# Main.net
KiCad netlist of a schematic drawn in Altium Designer
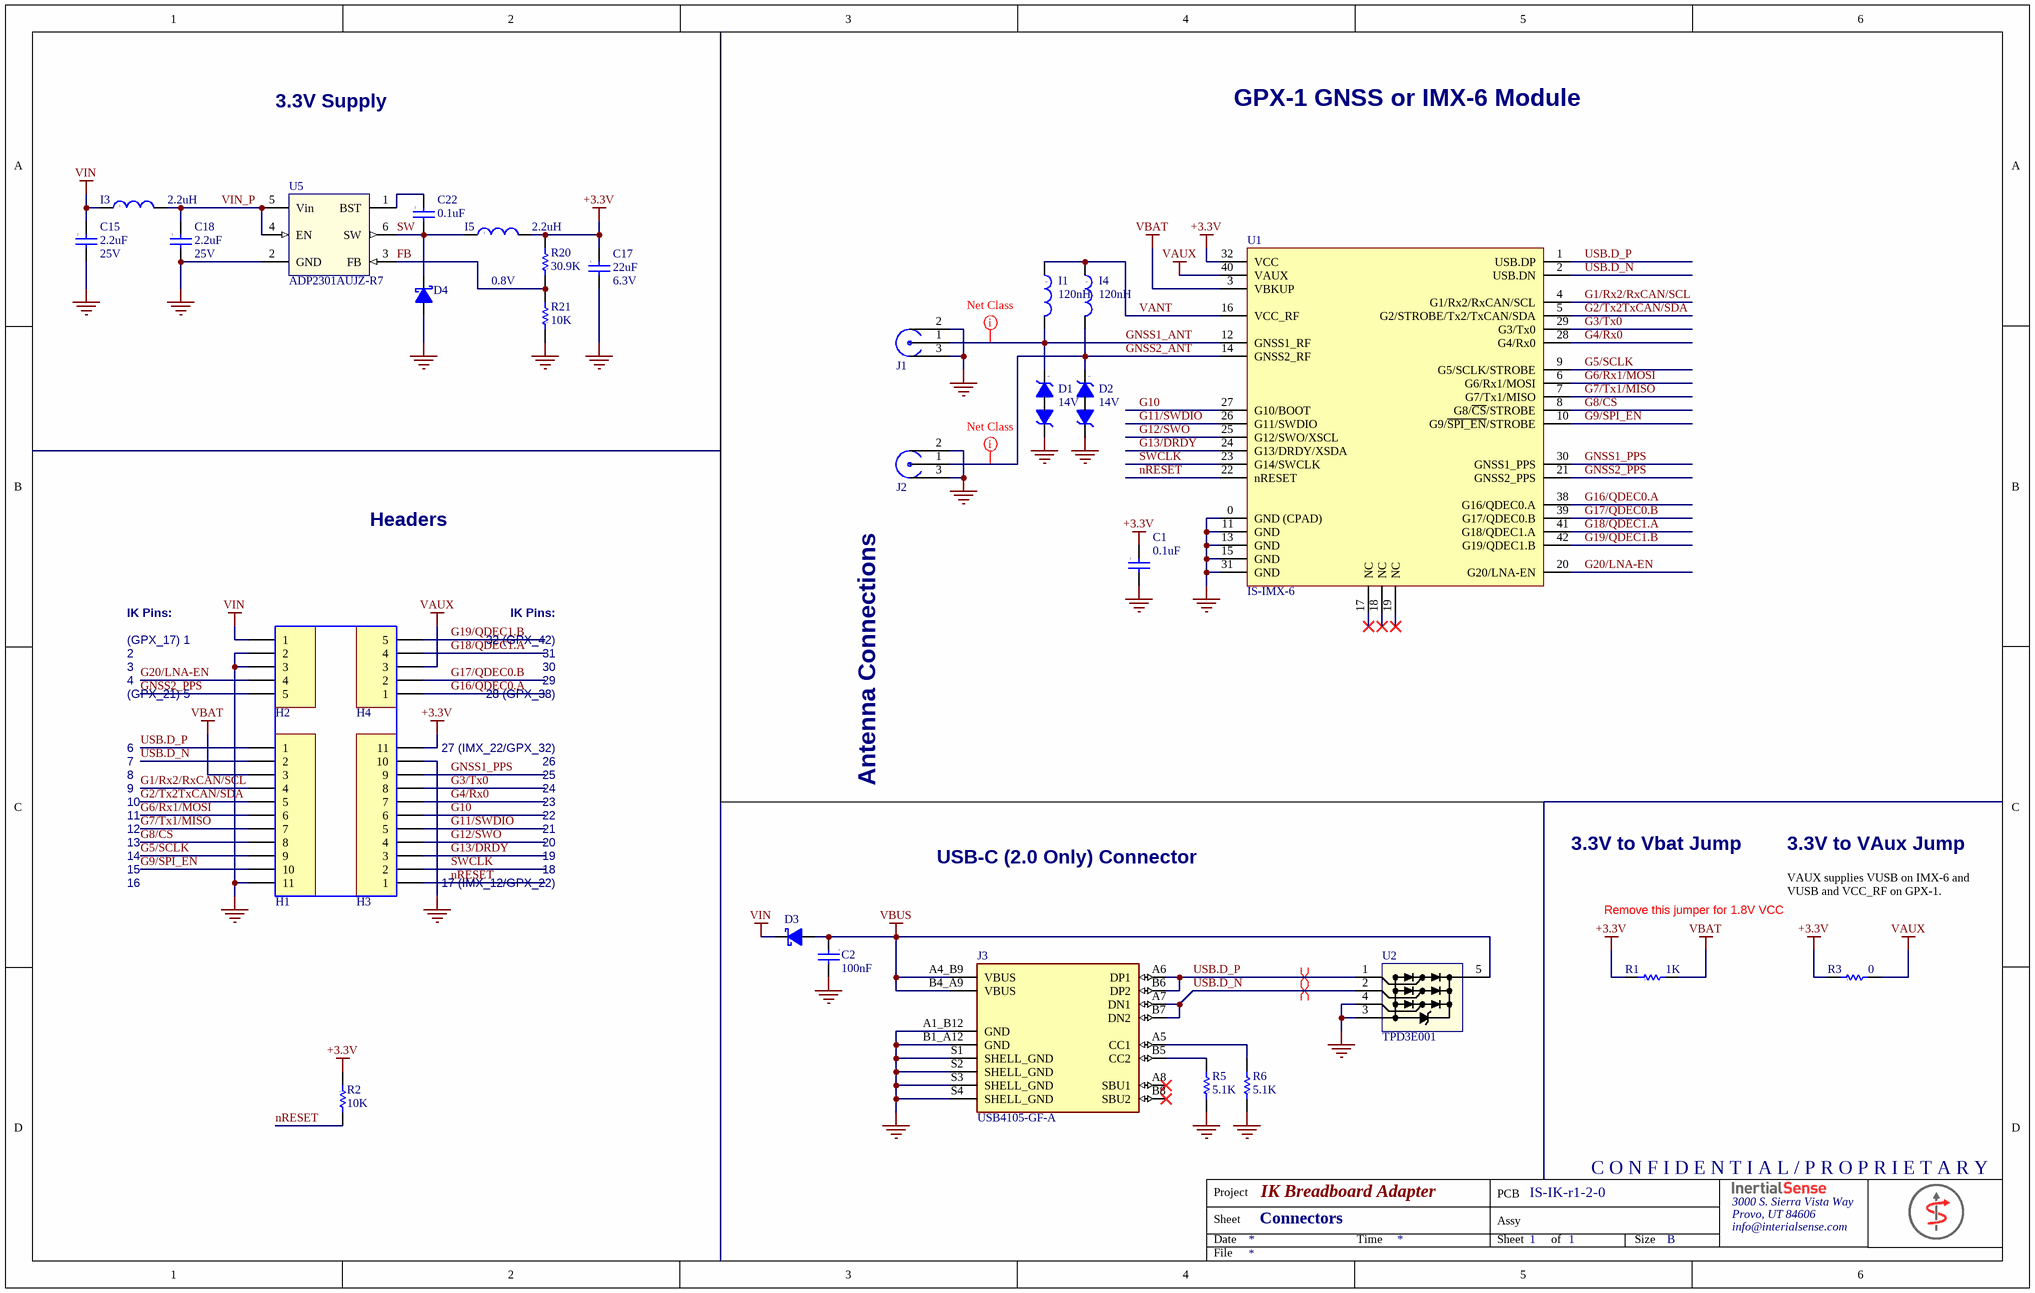
[diagram p0: Main.SchDoc]

(export (version "E")
  (design (tool "Eeschema 10.0.6"))
  (components
    (comp (ref "C1")
      (value "0.1uF")
      (footprint "0402")
      (description "CAP CER .10UF 50V X7R 10% 0402")
      (fields
        (field (name "MANUFACTURER") "TDK Corporation")
        (field (name "MANUFACTURER PART NUMBER") "C1005X7R1H104K")
        (field (name "PUBLISHER") "Altium Limited")
      )
      (libsource (lib "General") (part "Cap"))
    )
    (comp (ref "C2")
      (value "100nF")
      (footprint "0402")
      (description "CAP CER .10UF 50V X7R 10% 0402")
      (fields
        (field (name "MANUFACTURER") "TDK Corporation")
        (field (name "MANUFACTURER PART NUMBER") "C1005X7R1H104K")
        (field (name "PUBLISHER") "Altium Limited")
      )
      (libsource (lib "General") (part "Cap"))
    )
    (comp (ref "C15")
      (value "2.2uF")
      (footprint "0603")
      (description "CAP CER 2.2UF 25V X6S 0603")
      (fields
        (field (name "MANUFACTURER") "Murata")
        (field (name "MANUFACTURER PART NUMBER") "GRT188C81E225KE13D")
        (field (name "VOLTAGE RATING") "25V")
        (field (name "PUBLISHER") "Altium Limited")
      )
      (libsource (lib "General") (part "Cap"))
    )
    (comp (ref "C17")
      (value "22uF")
      (footprint "0603")
      (description "CAP CER 22UF 6.3V X6S 0603")
      (fields
        (field (name "MANUFACTURER") "Murata")
        (field (name "MANUFACTURER PART NUMBER") "GRM188C80J226ME15D")
        (field (name "VOLTAGE RATING") "6.3V")
        (field (name "PUBLISHER") "Altium Limited")
      )
      (libsource (lib "General") (part "Cap"))
    )
    (comp (ref "C18")
      (value "2.2uF")
      (footprint "0603")
      (description "CAP CER 2.2UF 25V X6S 0603")
      (fields
        (field (name "MANUFACTURER") "Murata")
        (field (name "MANUFACTURER PART NUMBER") "GRT188C81E225KE13D")
        (field (name "VOLTAGE RATING") "25V")
        (field (name "PUBLISHER") "Altium Limited")
      )
      (libsource (lib "General") (part "Cap"))
    )
    (comp (ref "C22")
      (value "0.1uF")
      (footprint "0402")
      (description "CAP CER 0.1UF 50V X7R 0402")
      (fields
        (field (name "MANUFACTURER") "TDK")
        (field (name "MANUFACTURER PART NUMBER") "CGA2B3X7R1H104K050BB")
        (field (name "PUBLISHER") "Altium Limited")
      )
      (libsource (lib "General") (part "Cap"))
    )
    (comp (ref "D1")
      (value "Diode - Bidirectional Zener")
      (footprint "R0402")
      (description "LITTELFUSE - PESD0402-140 - DIODE, ESD PROTECTION, 0402, FULL REEL")
      (fields
        (field (name "MANUFACTURER") "Littelfuse")
        (field (name "MANUFACTURER PART NUMBER") "PESD0402-140")
        (field (name "WORKING VOLTAGE") "14V")
      )
      (libsource (lib "General") (part "Diode - Bidirectional Zener"))
    )
    (comp (ref "D2")
      (value "Diode - Bidirectional Zener")
      (footprint "R0402")
      (description "LITTELFUSE - PESD0402-140 - DIODE, ESD PROTECTION, 0402, FULL REEL")
      (fields
        (field (name "MANUFACTURER") "Littelfuse")
        (field (name "MANUFACTURER PART NUMBER") "PESD0402-140")
        (field (name "WORKING VOLTAGE") "14V")
      )
      (libsource (lib "General") (part "Diode - Bidirectional Zener"))
    )
    (comp (ref "D3")
      (value "Diode - Schottky")
      (footprint "D0603B")
      (description "DIODE SCHOTTKY 30V 2A 0603")
      (fields
        (field (name "MANUFACTURER") "Vishay")
        (field (name "MANUFACTURER PART NUMBER") "VSKY20301608-G4-08")
      )
      (libsource (lib "General") (part "Diode - Schottky"))
    )
    (comp (ref "D4")
      (value "Diode - Schottky")
      (footprint "D0603B")
      (description "DIODE SCHOTTKY 30V 2A 0603")
      (fields
        (field (name "MANUFACTURER") "Vishay")
        (field (name "MANUFACTURER PART NUMBER") "VSKY20301608-G4-08")
      )
      (libsource (lib "General") (part "Diode - Schottky"))
    )
    (comp (ref "H1")
      (value "Hdr - 11pin")
      (footprint "Header-.1IN-1x11")
      (description "11 pin header")
      (libsource (lib "") (part "Hdr - 11pin_1"))
    )
    (comp (ref "H2")
      (value "Hdr - 5pin")
      (footprint "Header-.1IN-1x5")
      (description "5 pin header")
      (libsource (lib "") (part "Hdr - 5pin_1"))
    )
    (comp (ref "H3")
      (value "Hdr - 11pin")
      (footprint "Header-.1IN-1x11")
      (description "11 pin header")
      (libsource (lib "IS-IG-BB") (part "Hdr - 11pin"))
    )
    (comp (ref "H4")
      (value "Hdr - 5pin")
      (footprint "Header-.1IN-1x5")
      (description "5 pin header")
      (libsource (lib "IS-IG-BB") (part "Hdr - 5pin"))
    )
    (comp (ref "I1")
      (value "120nH")
      (footprint "0402")
      (description "Inductor RF Chip Wirewound 120nH 5% 100MHz 20Q-Factor 110mA 2.66Ohm DCR 0402 Paper T/R")
      (fields
        (field (name "MANUFACTURER") "Murata")
        (field (name "MANUFACTURER PART NUMBER") "LQW15ANR12J00D")
      )
      (libsource (lib "General") (part "Inductor"))
    )
    (comp (ref "I3")
      (value "2.2uH")
      (footprint "0806")
      (description "FIXED IND 2.2UH 1.2A 110 MOHM")
      (fields
        (field (name "MANUFACTURER") "TDK")
        (field (name "MANUFACTURER PART NUMBER") "MLP2016H2R2MT0S1")
      )
      (libsource (lib "General") (part "Inductor"))
    )
    (comp (ref "I4")
      (value "120nH")
      (footprint "0402")
      (description "Inductor RF Chip Wirewound 120nH 5% 100MHz 20Q-Factor 110mA 2.66Ohm DCR 0402 Paper T/R")
      (fields
        (field (name "MANUFACTURER") "Murata")
        (field (name "MANUFACTURER PART NUMBER") "LQW15ANR12J00D")
      )
      (libsource (lib "General") (part "Inductor"))
    )
    (comp (ref "I5")
      (value "2.2uH")
      (footprint "0806")
      (description "FIXED IND 2.2UH 1.2A 110 MOHM")
      (fields
        (field (name "MANUFACTURER") "TDK")
        (field (name "MANUFACTURER PART NUMBER") "MLP2016H2R2MT0S1")
      )
      (libsource (lib "General") (part "Inductor"))
    )
    (comp (ref "J1")
      (value "RF - GND x 2")
      (footprint "RF UMC SMD")
      (description "CONN UMC RCPT STR 50 OHM SMD")
      (fields
        (field (name "MANUFACTURER") "Emerson Network Power Connectivity Johnson")
        (field (name "MANUFACTURER PART NUMBER") "128-0711-201")
      )
      (libsource (lib "Connectors") (part "RF - GND x 2"))
    )
    (comp (ref "J2")
      (value "RF - GND x 2")
      (footprint "RF UMC SMD")
      (description "CONN UMC RCPT STR 50 OHM SMD")
      (fields
        (field (name "MANUFACTURER") "Emerson Network Power Connectivity Johnson")
        (field (name "MANUFACTURER PART NUMBER") "128-0711-201")
      )
      (libsource (lib "Connectors") (part "RF - GND x 2"))
    )
    (comp (ref "J3")
      (value "USB4105-GF-A")
      (footprint "GCT_USB4105-GF-A")
      (fields (field (name "MANUFACTURER") "GCT"))
      (libsource (lib "Connectors") (part "USB4105-GF-A"))
    )
    (comp (ref "R1")
      (value "1K")
      (footprint "R0402")
      (description "1 kOhms 1/16W Chip Resistor 0402 (1005 Metric) Moisture Resistant Thick Film")
      (fields
        (field (name "MANUFACTURER") "Yageo")
        (field (name "MANUFACTURER PART NUMBER") "RC0402FR-071KL")
      )
      (libsource (lib "General") (part "Res"))
    )
    (comp (ref "R2")
      (value "10K")
      (footprint "R0402")
      (description "10 kOhms 1/16W Chip Resistor 0402 (1005 Metric) Moisture Resistant Thick Film")
      (fields
        (field (name "MANUFACTURER") "Stackpole Electronics")
        (field (name "MANUFACTURER PART NUMBER") "RMCF0402FT10K0")
      )
      (libsource (lib "General") (part "Res"))
    )
    (comp (ref "R3")
      (value "0")
      (footprint "R0402")
      (description "0 Ohms 1/16W Chip Resistor 0402 (1005 Metric) Moisture Resistant Thick Film")
      (fields
        (field (name "MANUFACTURER") "Yageo")
        (field (name "MANUFACTURER PART NUMBER") "RC0402JR-070RL")
      )
      (libsource (lib "General") (part "Res"))
    )
    (comp (ref "R5")
      (value "5.1K")
      (footprint "R0402")
      (description "Res Thick Film 1.0 x 0.5 mm 5.1K Ohm 1% 0.063W(1/16W) 100ppm/ C Molded SMD Paper T/R")
      (fields
        (field (name "MANUFACTURER") "Yageo")
        (field (name "MANUFACTURER PART NUMBER") "RC0402FR-075K1L")
      )
      (libsource (lib "General") (part "Res"))
    )
    (comp (ref "R6")
      (value "5.1K")
      (footprint "R0402")
      (description "Res Thick Film 1.0 x 0.5 mm 5.1K Ohm 1% 0.063W(1/16W) 100ppm/ C Molded SMD Paper T/R")
      (fields
        (field (name "MANUFACTURER") "Yageo")
        (field (name "MANUFACTURER PART NUMBER") "RC0402FR-075K1L")
      )
      (libsource (lib "General") (part "Res"))
    )
    (comp (ref "R20")
      (value "30.9K")
      (footprint "R0402")
      (description "RES TF 30.9K OHM 1% 1/16W 0402")
      (fields
        (field (name "MANUFACTURER") "Stackpole Electronics Inc")
        (field (name "MANUFACTURER PART NUMBER") "RMCF0402FT30K9")
      )
      (libsource (lib "General") (part "Res"))
    )
    (comp (ref "R21")
      (value "10K")
      (footprint "R0402")
      (description "RES 10.0K OHM 1/16W 1% 0402 SMD")
      (fields
        (field (name "MANUFACTURER") "Yageo")
        (field (name "MANUFACTURER PART NUMBER") "RC0402FR-0710KL")
      )
      (libsource (lib "General") (part "Res"))
    )
    (comp (ref "U1")
      (value "IMX")
      (footprint "IS-GPX-1.0")
      (description "Inertial Sense IMX")
      (fields
        (field (name "MANUFACTURER") "Inertial Sense")
        (field (name "MANUFACTURER PART NUMBER") "IS-IMX-6")
      )
      (libsource (lib "IS-GPX-1") (part "IS-GPX-1.0"))
    )
    (comp (ref "U2")
      (value "TPD3E001")
      (footprint "SOTFL50P160X60-5N")
      (description "TVS DIODE 5.5V SOT5")
      (fields
        (field (name "MANUFACTURER") "Texas Instruments")
        (field (name "MANUFACTURER PART NUMBER") "TPD3E001DRLR")
      )
      (libsource (lib "ICs") (part "TPD3E001"))
    )
    (comp (ref "U5")
      (value "ADP2301")
      (footprint "MO-178-AB")
      (description "IC BUCK ADJ 1.2A 6TSOT")
      (fields
        (field (name "MANUFACTURER") "Analog Devices Inc")
        (field (name "MANUFACTURER PART NUMBER") "ADP2301AUJZ-R7")
      )
      (libsource (lib "ICs") (part "ADP2301"))
    )
  )
  (nets
    (net (code "1") (name "+3.3V") (class "Default")
      (node (ref "C1") (pin "1") (pinfunction "1_1") (pintype "passive"))
      (node (ref "C17") (pin "1") (pinfunction "1_1") (pintype "passive"))
      (node (ref "H3") (pin "11") (pinfunction "11_11") (pintype "passive"))
      (node (ref "I5") (pin "2") (pinfunction "2_2") (pintype "passive"))
      (node (ref "R1") (pin "1") (pinfunction "1_1") (pintype "passive"))
      (node (ref "R2") (pin "1") (pinfunction "1_1") (pintype "passive"))
      (node (ref "R20") (pin "2") (pinfunction "2_2") (pintype "passive"))
      (node (ref "R3") (pin "1") (pinfunction "1_1") (pintype "passive"))
      (node (ref "U1") (pin "32") (pinfunction "VCC_32") (pintype "power_in"))
    )
    (net (code "2") (name "/FB") (class "Default")
      (node (ref "R20") (pin "1") (pinfunction "1_1") (pintype "passive"))
      (node (ref "R21") (pin "2") (pinfunction "2_2") (pintype "passive"))
      (node (ref "U5") (pin "3") (pinfunction "FB_3") (pintype "input"))
    )
    (net (code "3") (name "/G1{slash}Rx2{slash}RxCAN{slash}SCL") (class "Default")
      (node (ref "H1") (pin "4") (pinfunction "4_4") (pintype "passive"))
      (node (ref "U1") (pin "4") (pinfunction "G1/Rx2/RxCAN/SCL_4") (pintype "passive"))
    )
    (net (code "4") (name "/G2{slash}Tx2TxCAN{slash}SDA") (class "Default")
      (node (ref "H1") (pin "5") (pinfunction "5_5") (pintype "passive"))
      (node (ref "U1") (pin "5") (pinfunction "G2/STROBE/Tx2/TxCAN/SDA_5") (pintype "passive"))
    )
    (net (code "5") (name "/G3{slash}Tx0") (class "Default")
      (node (ref "H3") (pin "8") (pinfunction "8_8") (pintype "passive"))
      (node (ref "U1") (pin "29") (pinfunction "G3/Tx0_29") (pintype "passive"))
    )
    (net (code "6") (name "/G4{slash}Rx0") (class "Default")
      (node (ref "H3") (pin "7") (pinfunction "7_7") (pintype "passive"))
      (node (ref "U1") (pin "28") (pinfunction "G4/Rx0_28") (pintype "passive"))
    )
    (net (code "7") (name "/G5{slash}SCLK") (class "Default")
      (node (ref "H1") (pin "9") (pinfunction "9_9") (pintype "passive"))
      (node (ref "U1") (pin "9") (pinfunction "G5/SCLK/STROBE_9") (pintype "passive"))
    )
    (net (code "8") (name "/G6{slash}Rx1{slash}MOSI") (class "Default")
      (node (ref "H1") (pin "6") (pinfunction "6_6") (pintype "passive"))
      (node (ref "U1") (pin "6") (pinfunction "G6/Rx1/MOSI_6") (pintype "passive"))
    )
    (net (code "9") (name "/G7{slash}Tx1{slash}MISO") (class "Default")
      (node (ref "H1") (pin "7") (pinfunction "7_7") (pintype "passive"))
      (node (ref "U1") (pin "7") (pinfunction "G7/Tx1/MISO_7") (pintype "passive"))
    )
    (net (code "10") (name "/G8{slash}~{CS}") (class "Default")
      (node (ref "H1") (pin "8") (pinfunction "8_8") (pintype "passive"))
      (node (ref "U1") (pin "8") (pinfunction "G8/~{CS}/STROBE_8") (pintype "passive"))
    )
    (net (code "11") (name "/G9{slash}~{SPI_EN}") (class "Default")
      (node (ref "H1") (pin "10") (pinfunction "10_10") (pintype "passive"))
      (node (ref "U1") (pin "10") (pinfunction "G9/~{SPI_EN}/STROBE_10") (pintype "passive"))
    )
    (net (code "12") (name "/G10") (class "Default")
      (node (ref "H3") (pin "6") (pinfunction "6_6") (pintype "passive"))
      (node (ref "U1") (pin "27") (pinfunction "G10/BOOT_27") (pintype "passive"))
    )
    (net (code "13") (name "/G11{slash}SWDIO") (class "Default")
      (node (ref "H3") (pin "5") (pinfunction "5_5") (pintype "passive"))
      (node (ref "U1") (pin "26") (pinfunction "G11/SWDIO_26") (pintype "passive"))
    )
    (net (code "14") (name "/G12{slash}SWO") (class "Default")
      (node (ref "H3") (pin "4") (pinfunction "4_4") (pintype "passive"))
      (node (ref "U1") (pin "25") (pinfunction "G12/SWO/XSCL_25") (pintype "passive"))
    )
    (net (code "15") (name "/G13{slash}DRDY") (class "Default")
      (node (ref "H3") (pin "3") (pinfunction "3_3") (pintype "passive"))
      (node (ref "U1") (pin "24") (pinfunction "G13/DRDY/XSDA_24") (pintype "passive"))
    )
    (net (code "16") (name "/G16{slash}QDEC0.A") (class "Default")
      (node (ref "H4") (pin "1") (pinfunction "1_1") (pintype "passive"))
      (node (ref "U1") (pin "38") (pinfunction "G16/QDEC0.A_38") (pintype "passive"))
    )
    (net (code "17") (name "/G17{slash}QDEC0.B") (class "Default")
      (node (ref "H4") (pin "2") (pinfunction "2_2") (pintype "passive"))
      (node (ref "U1") (pin "39") (pinfunction "G17/QDEC0.B_39") (pintype "passive"))
    )
    (net (code "18") (name "/G18{slash}QDEC1.A") (class "Default")
      (node (ref "H4") (pin "4") (pinfunction "4_4") (pintype "passive"))
      (node (ref "U1") (pin "41") (pinfunction "G18/QDEC1.A_41") (pintype "passive"))
    )
    (net (code "19") (name "/G19{slash}QDEC1.B") (class "Default")
      (node (ref "H4") (pin "5") (pinfunction "5_5") (pintype "passive"))
      (node (ref "U1") (pin "42") (pinfunction "G19/QDEC1.B_42") (pintype "passive"))
    )
    (net (code "20") (name "/G20{slash}LNA-EN") (class "Default")
      (node (ref "H2") (pin "4") (pinfunction "4_4") (pintype "passive"))
      (node (ref "U1") (pin "20") (pinfunction "G20/LNA-EN_20") (pintype "passive"))
    )
    (net (code "21") (name "/GNSS1_ANT") (class "Default")
      (node (ref "D1") (pin "1") (pinfunction "1_1") (pintype "passive"))
      (node (ref "I1") (pin "2") (pinfunction "2_2") (pintype "passive"))
      (node (ref "J1") (pin "1") (pinfunction "1_1") (pintype "passive"))
      (node (ref "U1") (pin "12") (pinfunction "GNSS1_RF_12") (pintype "passive"))
    )
    (net (code "22") (name "/GNSS1_PPS") (class "Default")
      (node (ref "H3") (pin "9") (pinfunction "9_9") (pintype "passive"))
      (node (ref "U1") (pin "30") (pinfunction "GNSS1_PPS_30") (pintype "passive"))
    )
    (net (code "23") (name "/GNSS2_ANT") (class "Default")
      (node (ref "D2") (pin "1") (pinfunction "1_1") (pintype "passive"))
      (node (ref "I4") (pin "2") (pinfunction "2_2") (pintype "passive"))
      (node (ref "J2") (pin "1") (pinfunction "1_1") (pintype "passive"))
      (node (ref "U1") (pin "14") (pinfunction "GNSS2_RF_14") (pintype "passive"))
    )
    (net (code "24") (name "/GNSS2_PPS") (class "Default")
      (node (ref "H2") (pin "5") (pinfunction "5_5") (pintype "passive"))
      (node (ref "U1") (pin "21") (pinfunction "GNSS2_PPS_21") (pintype "passive"))
    )
    (net (code "25") (name "/SW") (class "Default")
      (node (ref "C22") (pin "2") (pinfunction "2_2") (pintype "passive"))
      (node (ref "D4") (pin "C") (pinfunction "C_C") (pintype "passive"))
      (node (ref "I5") (pin "1") (pinfunction "1_1") (pintype "passive"))
      (node (ref "U5") (pin "6") (pinfunction "SW_6") (pintype "output"))
    )
    (net (code "26") (name "/SWCLK") (class "Default")
      (node (ref "H3") (pin "2") (pinfunction "2_2") (pintype "passive"))
      (node (ref "U1") (pin "23") (pinfunction "G14/SWCLK_23") (pintype "passive"))
    )
    (net (code "27") (name "/USB.D_N") (class "Default")
      (node (ref "H1") (pin "2") (pinfunction "2_2") (pintype "passive"))
      (node (ref "J3") (pin "A7") (pinfunction "DN1_A7") (pintype "bidirectional"))
      (node (ref "J3") (pin "B7") (pinfunction "DN2_B7") (pintype "bidirectional"))
      (node (ref "U1") (pin "2") (pinfunction "USB.DN_2") (pintype "passive"))
      (node (ref "U2") (pin "2") (pintype "passive"))
    )
    (net (code "28") (name "/USB.D_P") (class "Default")
      (node (ref "H1") (pin "1") (pinfunction "1_1") (pintype "passive"))
      (node (ref "J3") (pin "A6") (pinfunction "DP1_A6") (pintype "bidirectional"))
      (node (ref "J3") (pin "B6") (pinfunction "DP2_B6") (pintype "bidirectional"))
      (node (ref "U1") (pin "1") (pinfunction "USB.DP_1") (pintype "passive"))
      (node (ref "U2") (pin "1") (pintype "passive"))
    )
    (net (code "29") (name "/VANT") (class "Default")
      (node (ref "I1") (pin "1") (pinfunction "1_1") (pintype "passive"))
      (node (ref "I4") (pin "1") (pinfunction "1_1") (pintype "passive"))
      (node (ref "U1") (pin "16") (pinfunction "VCC_RF_16") (pintype "power_in"))
    )
    (net (code "30") (name "/VIN_P") (class "Default")
      (node (ref "C18") (pin "1") (pinfunction "1_1") (pintype "passive"))
      (node (ref "I3") (pin "2") (pinfunction "2_2") (pintype "passive"))
      (node (ref "U5") (pin "4") (pinfunction "EN_4") (pintype "input"))
      (node (ref "U5") (pin "5") (pinfunction "Vin_5") (pintype "power_in"))
    )
    (net (code "31") (name "/nRESET") (class "Default")
      (node (ref "H3") (pin "1") (pinfunction "1_1") (pintype "passive"))
      (node (ref "R2") (pin "2") (pinfunction "2_2") (pintype "passive"))
      (node (ref "U1") (pin "22") (pinfunction "nRESET_22") (pintype "passive"))
    )
    (net (code "32") (name "GND") (class "Default")
      (node (ref "C1") (pin "2") (pinfunction "2_2") (pintype "passive"))
      (node (ref "C15") (pin "2") (pinfunction "2_2") (pintype "passive"))
      (node (ref "C17") (pin "2") (pinfunction "2_2") (pintype "passive"))
      (node (ref "C18") (pin "2") (pinfunction "2_2") (pintype "passive"))
      (node (ref "C2") (pin "2") (pinfunction "2_2") (pintype "passive"))
      (node (ref "D1") (pin "2") (pinfunction "2_2") (pintype "passive"))
      (node (ref "D2") (pin "2") (pinfunction "2_2") (pintype "passive"))
      (node (ref "D4") (pin "A") (pinfunction "A_A") (pintype "passive"))
      (node (ref "H1") (pin "11") (pinfunction "11_11") (pintype "passive"))
      (node (ref "H2") (pin "2") (pinfunction "2_2") (pintype "passive"))
      (node (ref "H2") (pin "3") (pinfunction "3_3") (pintype "passive"))
      (node (ref "H3") (pin "10") (pinfunction "10_10") (pintype "passive"))
      (node (ref "J1") (pin "2") (pinfunction "2_2") (pintype "passive"))
      (node (ref "J1") (pin "3") (pinfunction "3_3") (pintype "passive"))
      (node (ref "J2") (pin "2") (pinfunction "2_2") (pintype "passive"))
      (node (ref "J2") (pin "3") (pinfunction "3_3") (pintype "passive"))
      (node (ref "J3") (pin "A1_B12") (pinfunction "GND_A1_B12") (pintype "power_in"))
      (node (ref "J3") (pin "B1_A12") (pinfunction "GND_B1_A12") (pintype "power_in"))
      (node (ref "J3") (pin "S1") (pinfunction "SHELL_GND_S1") (pintype "power_in"))
      (node (ref "J3") (pin "S2") (pinfunction "SHELL_GND_S2") (pintype "power_in"))
      (node (ref "J3") (pin "S3") (pinfunction "SHELL_GND_S3") (pintype "power_in"))
      (node (ref "J3") (pin "S4") (pinfunction "SHELL_GND_S4") (pintype "power_in"))
      (node (ref "R21") (pin "1") (pinfunction "1_1") (pintype "passive"))
      (node (ref "R5") (pin "1") (pinfunction "1_1") (pintype "passive"))
      (node (ref "R6") (pin "1") (pinfunction "1_1") (pintype "passive"))
      (node (ref "U1") (pin "0") (pinfunction "GND_(CPAD)_0") (pintype "power_in"))
      (node (ref "U1") (pin "11") (pinfunction "GND_11") (pintype "power_in"))
      (node (ref "U1") (pin "13") (pinfunction "GND_13") (pintype "power_in"))
      (node (ref "U1") (pin "15") (pinfunction "GND_15") (pintype "power_in"))
      (node (ref "U1") (pin "31") (pinfunction "GND_31") (pintype "power_in"))
      (node (ref "U2") (pin "3") (pintype "passive"))
      (node (ref "U2") (pin "4") (pinfunction "nc_4") (pintype "passive"))
      (node (ref "U5") (pin "2") (pinfunction "GND_2") (pintype "power_in"))
    )
    (net (code "33") (name "Net-(J3-CC1)") (class "Default")
      (node (ref "J3") (pin "A5") (pinfunction "CC1_A5") (pintype "bidirectional"))
      (node (ref "R6") (pin "2") (pinfunction "2_2") (pintype "passive"))
    )
    (net (code "34") (name "Net-(J3-CC2)") (class "Default")
      (node (ref "J3") (pin "B5") (pinfunction "CC2_B5") (pintype "bidirectional"))
      (node (ref "R5") (pin "2") (pinfunction "2_2") (pintype "passive"))
    )
    (net (code "35") (name "Net-(U5-BST)") (class "Default")
      (node (ref "C22") (pin "1") (pinfunction "1_1") (pintype "passive"))
      (node (ref "U5") (pin "1") (pinfunction "BST_1") (pintype "passive"))
    )
    (net (code "36") (name "VAUX") (class "Default")
      (node (ref "H4") (pin "3") (pinfunction "3_3") (pintype "passive"))
      (node (ref "R3") (pin "2") (pinfunction "2_2") (pintype "passive"))
      (node (ref "U1") (pin "40") (pinfunction "VAUX_40") (pintype "power_in"))
    )
    (net (code "37") (name "VBAT") (class "Default")
      (node (ref "H1") (pin "3") (pinfunction "3_3") (pintype "passive"))
      (node (ref "R1") (pin "2") (pinfunction "2_2") (pintype "passive"))
      (node (ref "U1") (pin "3") (pinfunction "VBKUP_3") (pintype "passive"))
    )
    (net (code "38") (name "VBUS") (class "Default")
      (node (ref "C2") (pin "1") (pinfunction "1_1") (pintype "passive"))
      (node (ref "D3") (pin "A") (pinfunction "A_A") (pintype "passive"))
      (node (ref "J3") (pin "A4_B9") (pinfunction "VBUS_A4_B9") (pintype "passive"))
      (node (ref "J3") (pin "B4_A9") (pinfunction "VBUS_B4_A9") (pintype "passive"))
      (node (ref "U2") (pin "5") (pinfunction "nc_5") (pintype "passive"))
    )
    (net (code "39") (name "VIN") (class "Default")
      (node (ref "C15") (pin "1") (pinfunction "1_1") (pintype "passive"))
      (node (ref "D3") (pin "C") (pinfunction "C_C") (pintype "passive"))
      (node (ref "H2") (pin "1") (pinfunction "1_1") (pintype "passive"))
      (node (ref "I3") (pin "1") (pinfunction "1_1") (pintype "passive"))
    )
    (net (code "40") (name "unconnected-(J3-SBU1-PadA8)") (class "Default")
      (node (ref "J3") (pin "A8") (pinfunction "SBU1_A8") (pintype "bidirectional+no_connect"))
    )
    (net (code "41") (name "unconnected-(J3-SBU2-PadB8)") (class "Default")
      (node (ref "J3") (pin "B8") (pinfunction "SBU2_B8") (pintype "bidirectional+no_connect"))
    )
    (net (code "42") (name "unconnected-(U1-NC-Pad17)") (class "Default")
      (node (ref "U1") (pin "17") (pinfunction "NC_17") (pintype "passive+no_connect"))
    )
    (net (code "43") (name "unconnected-(U1-NC-Pad18)") (class "Default")
      (node (ref "U1") (pin "18") (pinfunction "NC_18") (pintype "passive+no_connect"))
    )
    (net (code "44") (name "unconnected-(U1-NC-Pad19)") (class "Default")
      (node (ref "U1") (pin "19") (pinfunction "NC_19") (pintype "passive+no_connect"))
    )
  )
)
